# Power_Socket_nrf24_dil.net
KiCad netlist of a schematic drawn in EAGLE
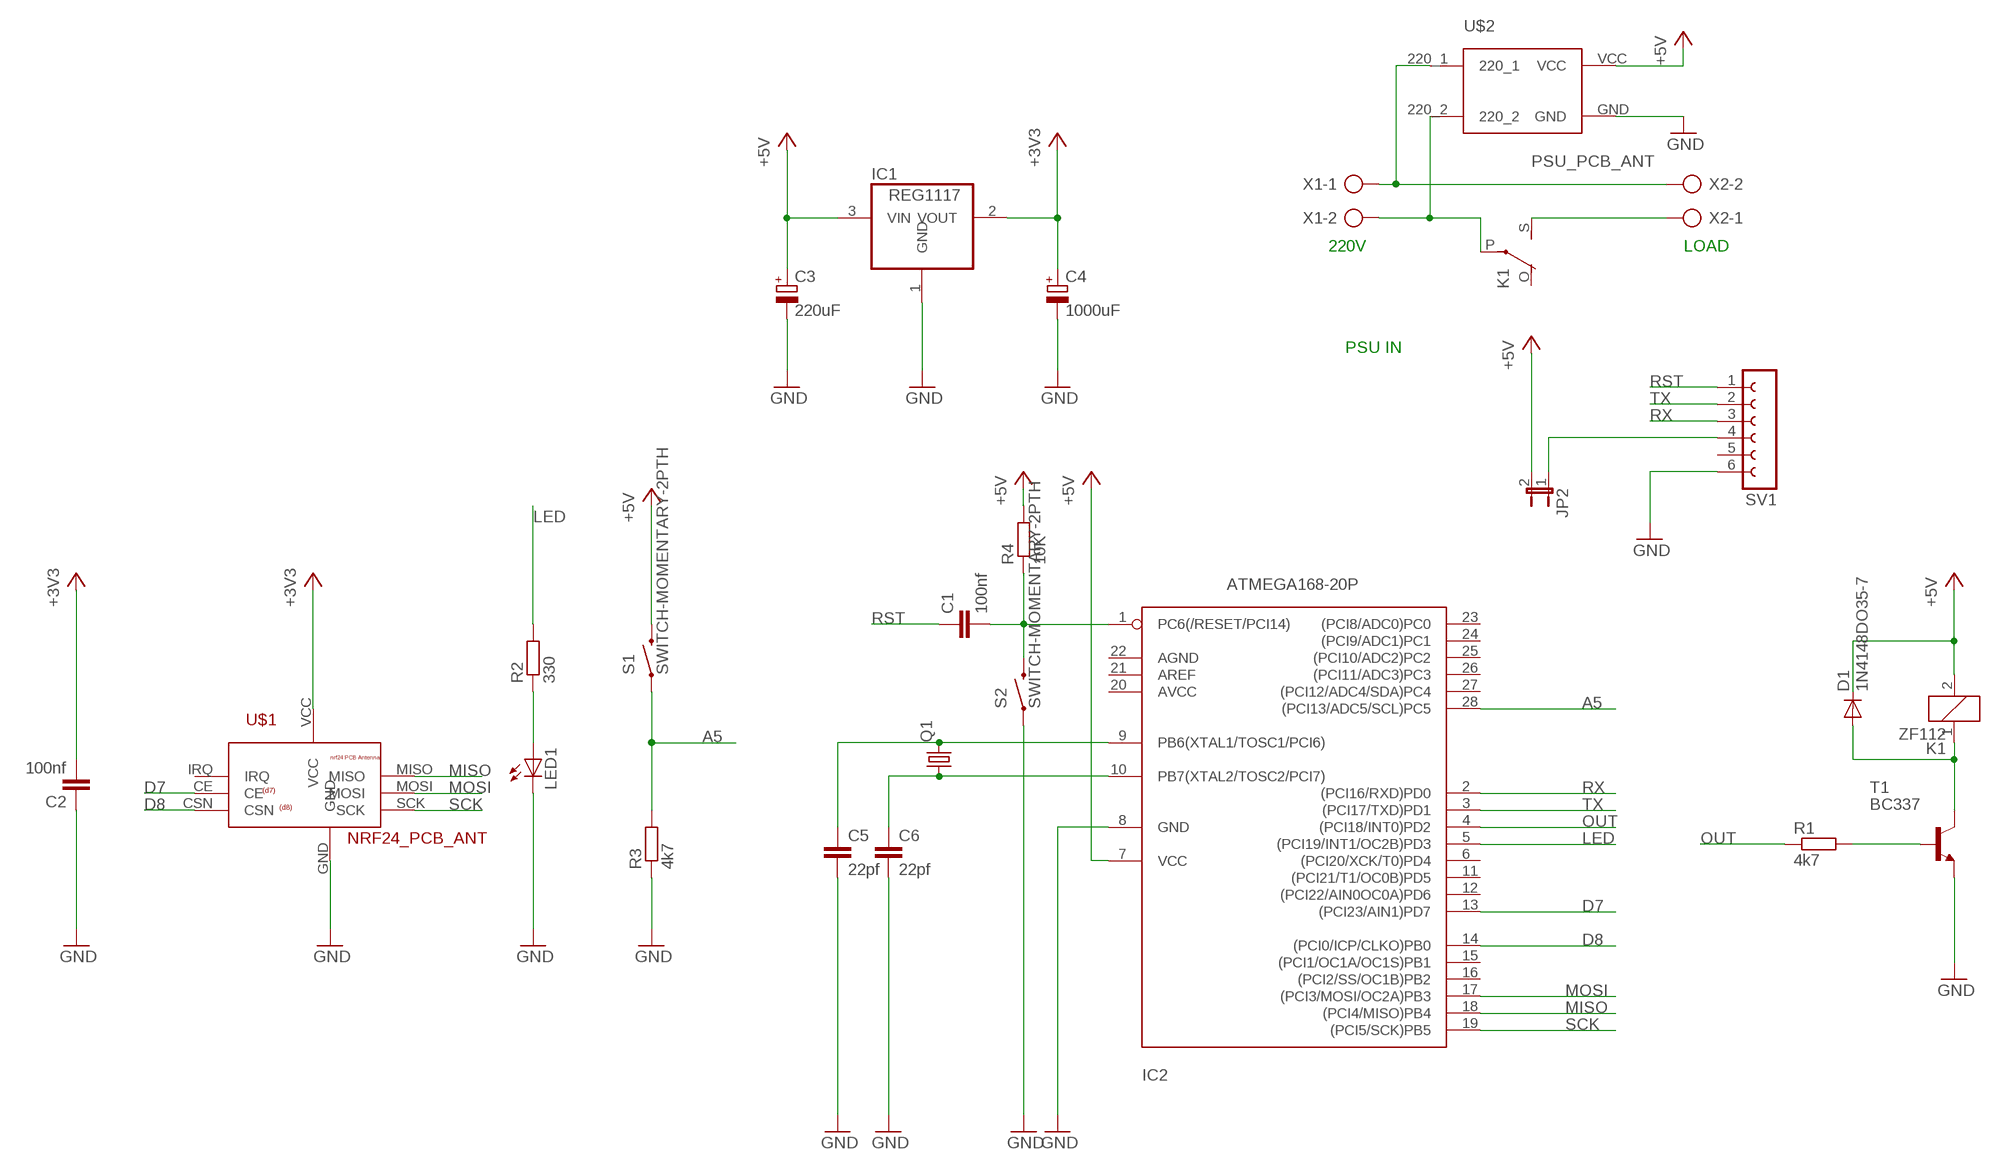
[diagram p0: schematic, sheet 1]

(export (version "E")
  (design (tool "Eeschema 10.0.6"))
  (components
    (comp (ref "C1")
      (value "100nf")
      (footprint "eagle-import:C1206")
      (libsource (lib "eagle-import") (part "C-EUC1206"))
    )
    (comp (ref "C2")
      (value "100nf")
      (footprint "eagle-import:C1206")
      (libsource (lib "eagle-import") (part "C-EUC1206"))
    )
    (comp (ref "C3")
      (value "220uF")
      (footprint "eagle-import:E2,5-6")
      (libsource (lib "eagle-import") (part "CPOL-EUE2.5-6"))
    )
    (comp (ref "C4")
      (value "1000uF")
      (footprint "eagle-import:E2,5-6")
      (libsource (lib "eagle-import") (part "CPOL-EUE2.5-6"))
    )
    (comp (ref "C5")
      (value "22pf")
      (footprint "eagle-import:C0805K")
      (libsource (lib "eagle-import") (part "C-EUC0805K"))
    )
    (comp (ref "C6")
      (value "22pf")
      (footprint "eagle-import:C0805K")
      (libsource (lib "eagle-import") (part "C-EUC0805K"))
    )
    (comp (ref "D1")
      (value "1N4148DO35-7")
      (footprint "eagle-import:DO35-7")
      (libsource (lib "eagle-import") (part "1N4148DO35-7"))
    )
    (comp (ref "IC1")
      (value "REG1117")
      (footprint "eagle-import:SOT223")
      (libsource (lib "eagle-import") (part "REG1117"))
    )
    (comp (ref "IC2")
      (value "ATMEGA168-20P")
      (footprint "eagle-import:DIL28-3")
      (libsource (lib "eagle-import") (part "ATMEGA168P-20"))
    )
    (comp (ref "JP2")
      (value "JUMPER-2PTH_LOCK")
      (footprint "eagle-import:1X02_LOCK")
      (libsource (lib "eagle-import") (part "JUMPER-2PTH_LOCK"))
    )
    (comp (ref "K1")
      (value "ZF112")
      (footprint "eagle-import:ZF112")
      (libsource (lib "eagle-import") (part "ZF112"))
    )
    (comp (ref "LED1")
      (value "LED3MM")
      (footprint "eagle-import:LED3MM")
      (libsource (lib "eagle-import") (part "LED3MM"))
    )
    (comp (ref "Q1")
      (value "CRYSTALHC49UV")
      (footprint "eagle-import:HC49U-V")
      (libsource (lib "eagle-import") (part "CRYSTALHC49UV"))
    )
    (comp (ref "R1")
      (value "4k7")
      (footprint "eagle-import:0207_10")
      (libsource (lib "eagle-import") (part "R-EU_0207/10"))
    )
    (comp (ref "R2")
      (value "330")
      (footprint "eagle-import:0207_10")
      (libsource (lib "eagle-import") (part "R-EU_0207/10"))
    )
    (comp (ref "R3")
      (value "4k7")
      (footprint "eagle-import:0207_10")
      (libsource (lib "eagle-import") (part "R-EU_0207/10"))
    )
    (comp (ref "R4")
      (value "10K")
      (footprint "eagle-import:0207_10")
      (libsource (lib "eagle-import") (part "R-EU_0207/10"))
    )
    (comp (ref "S1")
      (value "SWITCH-MOMENTARY-2PTH")
      (footprint "eagle-import:TACTILE-PTH")
      (libsource (lib "eagle-import") (part "SWITCH-MOMENTARY-2PTH"))
    )
    (comp (ref "S2")
      (value "SWITCH-MOMENTARY-2PTH")
      (footprint "eagle-import:TACTILE-PTH")
      (libsource (lib "eagle-import") (part "SWITCH-MOMENTARY-2PTH"))
    )
    (comp (ref "SV1")
      (value "FE06-1")
      (footprint "eagle-import:FE06")
      (libsource (lib "eagle-import") (part "FE06-1"))
    )
    (comp (ref "T1")
      (value "BC337")
      (footprint "eagle-import:TO92")
      (libsource (lib "eagle-import") (part "BC337"))
    )
    (comp (ref "U$1")
      (value "NRF24_PCB_ANT")
      (footprint "eagle-import:NRF24_PCB_ANT")
      (libsource (lib "eagle-import") (part "NRF24_PCB_ANT"))
    )
    (comp (ref "U$2")
      (value "PSU_PCB_ANT")
      (footprint "eagle-import:PSU_PCB_600MA")
      (libsource (lib "eagle-import") (part "PSU_PCB_ANT"))
    )
    (comp (ref "X1")
      (value "AK300/2")
      (footprint "eagle-import:AK300_2")
      (libsource (lib "eagle-import") (part "AK300/2"))
    )
    (comp (ref "X2")
      (value "AK300/2")
      (footprint "eagle-import:AK300_2")
      (libsource (lib "eagle-import") (part "AK300/2"))
    )
  )
  (nets
    (net (code "1") (name "+3V3") (class "Default")
      (node (ref "C2") (pin "2") (pinfunction "2_2") (pintype "passive"))
      (node (ref "C4") (pin "+") (pinfunction "+_+") (pintype "passive"))
      (node (ref "IC1") (pin "2") (pinfunction "VOUT_2") (pintype "output"))
      (node (ref "U$1") (pin "VCC") (pinfunction "VCC_VCC") (pintype "bidirectional"))
    )
    (net (code "2") (name "+5V") (class "Default")
      (node (ref "C3") (pin "+") (pinfunction "+_+") (pintype "passive"))
      (node (ref "D1") (pin "C") (pinfunction "C_C") (pintype "passive"))
      (node (ref "IC1") (pin "3") (pinfunction "VIN_3") (pintype "input"))
      (node (ref "IC2") (pin "7") (pinfunction "VCC_7") (pintype "bidirectional"))
      (node (ref "JP2") (pin "2") (pinfunction "2_2") (pintype "passive"))
      (node (ref "K1") (pin "2") (pinfunction "2_2") (pintype "passive"))
      (node (ref "R4") (pin "2") (pinfunction "2_2") (pintype "passive"))
      (node (ref "S1") (pin "3") (pinfunction "2_3") (pintype "passive"))
      (node (ref "U$2") (pin "VCC") (pinfunction "VCC_VCC") (pintype "bidirectional"))
    )
    (net (code "3") (name "/A5") (class "Default")
      (node (ref "IC2") (pin "28") (pinfunction "(PCI13/ADC5/SCL)PC5_28") (pintype "bidirectional"))
      (node (ref "R3") (pin "2") (pinfunction "2_2") (pintype "passive"))
      (node (ref "S1") (pin "1") (pinfunction "1_1") (pintype "passive"))
    )
    (net (code "4") (name "/D7") (class "Default")
      (node (ref "IC2") (pin "13") (pinfunction "(PCI23/AIN1)PD7_13") (pintype "bidirectional"))
      (node (ref "U$1") (pin "CE") (pinfunction "CE_CE") (pintype "bidirectional"))
    )
    (net (code "5") (name "/D8") (class "Default")
      (node (ref "IC2") (pin "14") (pinfunction "(PCI0/ICP/CLKO)PB0_14") (pintype "bidirectional"))
      (node (ref "U$1") (pin "CSN") (pinfunction "CSN_CSN") (pintype "bidirectional"))
    )
    (net (code "6") (name "/LED") (class "Default")
      (node (ref "IC2") (pin "5") (pinfunction "(PCI19/INT1/OC2B)PD3_5") (pintype "bidirectional"))
      (node (ref "R2") (pin "2") (pinfunction "2_2") (pintype "passive"))
    )
    (net (code "7") (name "/MISO") (class "Default")
      (node (ref "IC2") (pin "18") (pinfunction "(PCI4/MISO)PB4_18") (pintype "bidirectional"))
      (node (ref "U$1") (pin "MISO") (pinfunction "MISO_MISO") (pintype "bidirectional"))
    )
    (net (code "8") (name "/MOSI") (class "Default")
      (node (ref "IC2") (pin "17") (pinfunction "(PCI3/MOSI/OC2A)PB3_17") (pintype "bidirectional"))
      (node (ref "U$1") (pin "MOSI") (pinfunction "MOSI_MOSI") (pintype "bidirectional"))
    )
    (net (code "9") (name "/OUT") (class "Default")
      (node (ref "IC2") (pin "4") (pinfunction "(PCI18/INT0)PD2_4") (pintype "bidirectional"))
      (node (ref "R1") (pin "1") (pinfunction "1_1") (pintype "passive"))
    )
    (net (code "10") (name "/RST") (class "Default")
      (node (ref "C1") (pin "1") (pinfunction "1_1") (pintype "passive"))
      (node (ref "SV1") (pin "1") (pinfunction "1_1") (pintype "passive"))
    )
    (net (code "11") (name "/RX") (class "Default")
      (node (ref "IC2") (pin "2") (pinfunction "(PCI16/RXD)PD0_2") (pintype "bidirectional"))
      (node (ref "SV1") (pin "3") (pinfunction "3_3") (pintype "passive"))
    )
    (net (code "12") (name "/SCK") (class "Default")
      (node (ref "IC2") (pin "19") (pinfunction "(PCI5/SCK)PB5_19") (pintype "bidirectional"))
      (node (ref "U$1") (pin "SCK") (pinfunction "SCK_SCK") (pintype "bidirectional"))
    )
    (net (code "13") (name "/TX") (class "Default")
      (node (ref "IC2") (pin "3") (pinfunction "(PCI17/TXD)PD1_3") (pintype "bidirectional"))
      (node (ref "SV1") (pin "2") (pinfunction "2_2") (pintype "passive"))
    )
    (net (code "14") (name "GND") (class "Default")
      (node (ref "C2") (pin "1") (pinfunction "1_1") (pintype "passive"))
      (node (ref "C3") (pin "-") (pinfunction "-_-") (pintype "passive"))
      (node (ref "C4") (pin "-") (pinfunction "-_-") (pintype "passive"))
      (node (ref "C5") (pin "2") (pinfunction "2_2") (pintype "passive"))
      (node (ref "C6") (pin "2") (pinfunction "2_2") (pintype "passive"))
      (node (ref "IC1") (pin "1") (pinfunction "GND_1") (pintype "power_in"))
      (node (ref "IC2") (pin "8") (pinfunction "GND_8") (pintype "bidirectional"))
      (node (ref "LED1") (pin "K") (pinfunction "C_K") (pintype "passive"))
      (node (ref "R3") (pin "1") (pinfunction "1_1") (pintype "passive"))
      (node (ref "S2") (pin "1") (pinfunction "1_1") (pintype "passive"))
      (node (ref "SV1") (pin "6") (pinfunction "6_6") (pintype "passive"))
      (node (ref "T1") (pin "1") (pinfunction "E_1") (pintype "passive"))
      (node (ref "U$1") (pin "GND") (pinfunction "GND_GND") (pintype "bidirectional"))
      (node (ref "U$2") (pin "GND") (pinfunction "GND_GND") (pintype "bidirectional"))
    )
    (net (code "15") (name "Net-(IC2-PB6(XTAL1{slash}TOSC1{slash}PCI6))") (class "Default")
      (node (ref "C5") (pin "1") (pinfunction "1_1") (pintype "passive"))
      (node (ref "IC2") (pin "9") (pinfunction "PB6(XTAL1/TOSC1/PCI6)_9") (pintype "bidirectional"))
      (node (ref "Q1") (pin "2") (pinfunction "2_2") (pintype "passive"))
    )
    (net (code "16") (name "Net-(IC2-PB7(XTAL2{slash}TOSC2{slash}PCI7))") (class "Default")
      (node (ref "C6") (pin "1") (pinfunction "1_1") (pintype "passive"))
      (node (ref "IC2") (pin "10") (pinfunction "PB7(XTAL2/TOSC2/PCI7)_10") (pintype "bidirectional"))
      (node (ref "Q1") (pin "1") (pinfunction "1_1") (pintype "passive"))
    )
    (net (code "17") (name "Net-(IC2-PC6({slash}RESET{slash}PCI14))") (class "Default")
      (node (ref "C1") (pin "2") (pinfunction "2_2") (pintype "passive"))
      (node (ref "IC2") (pin "1") (pinfunction "PC6(/RESET/PCI14)_1") (pintype "bidirectional"))
      (node (ref "R4") (pin "1") (pinfunction "1_1") (pintype "passive"))
      (node (ref "S2") (pin "3") (pinfunction "2_3") (pintype "passive"))
    )
    (net (code "18") (name "Net-(JP2-Pad1)") (class "Default")
      (node (ref "JP2") (pin "1") (pinfunction "1_1") (pintype "passive"))
      (node (ref "SV1") (pin "4") (pinfunction "4_4") (pintype "passive"))
    )
    (net (code "19") (name "Net-(LED1-PadA)") (class "Default")
      (node (ref "LED1") (pin "A") (pinfunction "A_A") (pintype "passive"))
      (node (ref "R2") (pin "1") (pinfunction "1_1") (pintype "passive"))
    )
    (net (code "20") (name "Net-(T1-B)") (class "Default")
      (node (ref "R1") (pin "2") (pinfunction "2_2") (pintype "passive"))
      (node (ref "T1") (pin "2") (pinfunction "B_2") (pintype "passive"))
    )
    (net (code "21") (name "Net-(T1-C)") (class "Default")
      (node (ref "D1") (pin "A") (pinfunction "A_A") (pintype "passive"))
      (node (ref "K1") (pin "1") (pinfunction "1_1") (pintype "passive"))
      (node (ref "T1") (pin "3") (pinfunction "C_3") (pintype "passive"))
    )
    (net (code "22") (name "Net-(X1A-KL)") (class "Default")
      (node (ref "U$2") (pin "220_1") (pinfunction "220_1_220_1") (pintype "bidirectional"))
      (node (ref "X1") (pin "1") (pinfunction "KL_1") (pintype "passive"))
      (node (ref "X2") (pin "2") (pinfunction "KL_2") (pintype "passive"))
    )
    (net (code "23") (name "Net-(X1B-KL)") (class "Default")
      (node (ref "K1") (pin "P") (pinfunction "P_P") (pintype "passive"))
      (node (ref "U$2") (pin "220_2") (pinfunction "220_2_220_2") (pintype "bidirectional"))
      (node (ref "X1") (pin "2") (pinfunction "KL_2") (pintype "passive"))
    )
    (net (code "24") (name "Net-(X2A-KL)") (class "Default")
      (node (ref "K1") (pin "S") (pinfunction "S_S") (pintype "passive"))
      (node (ref "X2") (pin "1") (pinfunction "KL_1") (pintype "passive"))
    )
    (net (code "25") (name "unconnected-(IC2-(PCI1{slash}OC1A{slash}OC1S)PB1-Pad15)") (class "Default")
      (node (ref "IC2") (pin "15") (pinfunction "(PCI1/OC1A/OC1S)PB1_15") (pintype "bidirectional"))
    )
    (net (code "26") (name "unconnected-(IC2-(PCI2{slash}SS{slash}OC1B)PB2-Pad16)") (class "Default")
      (node (ref "IC2") (pin "16") (pinfunction "(PCI2/SS/OC1B)PB2_16") (pintype "bidirectional"))
    )
    (net (code "27") (name "unconnected-(IC2-(PCI8{slash}ADC0)PC0-Pad23)") (class "Default")
      (node (ref "IC2") (pin "23") (pinfunction "(PCI8/ADC0)PC0_23") (pintype "bidirectional"))
    )
    (net (code "28") (name "unconnected-(IC2-(PCI9{slash}ADC1)PC1-Pad24)") (class "Default")
      (node (ref "IC2") (pin "24") (pinfunction "(PCI9/ADC1)PC1_24") (pintype "bidirectional"))
    )
    (net (code "29") (name "unconnected-(IC2-(PCI10{slash}ADC2)PC2-Pad25)") (class "Default")
      (node (ref "IC2") (pin "25") (pinfunction "(PCI10/ADC2)PC2_25") (pintype "bidirectional"))
    )
    (net (code "30") (name "unconnected-(IC2-(PCI11{slash}ADC3)PC3-Pad26)") (class "Default")
      (node (ref "IC2") (pin "26") (pinfunction "(PCI11/ADC3)PC3_26") (pintype "bidirectional"))
    )
    (net (code "31") (name "unconnected-(IC2-(PCI12{slash}ADC4{slash}SDA)PC4-Pad27)") (class "Default")
      (node (ref "IC2") (pin "27") (pinfunction "(PCI12/ADC4/SDA)PC4_27") (pintype "bidirectional"))
    )
    (net (code "32") (name "unconnected-(IC2-(PCI20{slash}XCK{slash}T0)PD4-Pad6)") (class "Default")
      (node (ref "IC2") (pin "6") (pinfunction "(PCI20/XCK/T0)PD4_6") (pintype "bidirectional"))
    )
    (net (code "33") (name "unconnected-(IC2-(PCI21{slash}T1{slash}OC0B)PD5-Pad11)") (class "Default")
      (node (ref "IC2") (pin "11") (pinfunction "(PCI21/T1/OC0B)PD5_11") (pintype "bidirectional"))
    )
    (net (code "34") (name "unconnected-(IC2-(PCI22{slash}AIN0OC0A)PD6-Pad12)") (class "Default")
      (node (ref "IC2") (pin "12") (pinfunction "(PCI22/AIN0OC0A)PD6_12") (pintype "bidirectional"))
    )
    (net (code "35") (name "unconnected-(IC2-AGND-Pad22)") (class "Default")
      (node (ref "IC2") (pin "22") (pinfunction "AGND_22") (pintype "bidirectional"))
    )
    (net (code "36") (name "unconnected-(IC2-AREF-Pad21)") (class "Default")
      (node (ref "IC2") (pin "21") (pinfunction "AREF_21") (pintype "bidirectional"))
    )
    (net (code "37") (name "unconnected-(IC2-AVCC-Pad20)") (class "Default")
      (node (ref "IC2") (pin "20") (pinfunction "AVCC_20") (pintype "bidirectional"))
    )
    (net (code "38") (name "unconnected-(K1-PadO)") (class "Default")
      (node (ref "K1") (pin "O") (pinfunction "O_O") (pintype "passive"))
    )
    (net (code "39") (name "unconnected-(SV1-Pad5)") (class "Default")
      (node (ref "SV1") (pin "5") (pinfunction "5_5") (pintype "passive"))
    )
    (net (code "40") (name "unconnected-(U$1-PadIRQ)") (class "Default")
      (node (ref "U$1") (pin "IRQ") (pinfunction "IRQ_IRQ") (pintype "bidirectional"))
    )
  )
)
